# SixPotatoeV6.net
KiCad netlist of a schematic drawn in EAGLE
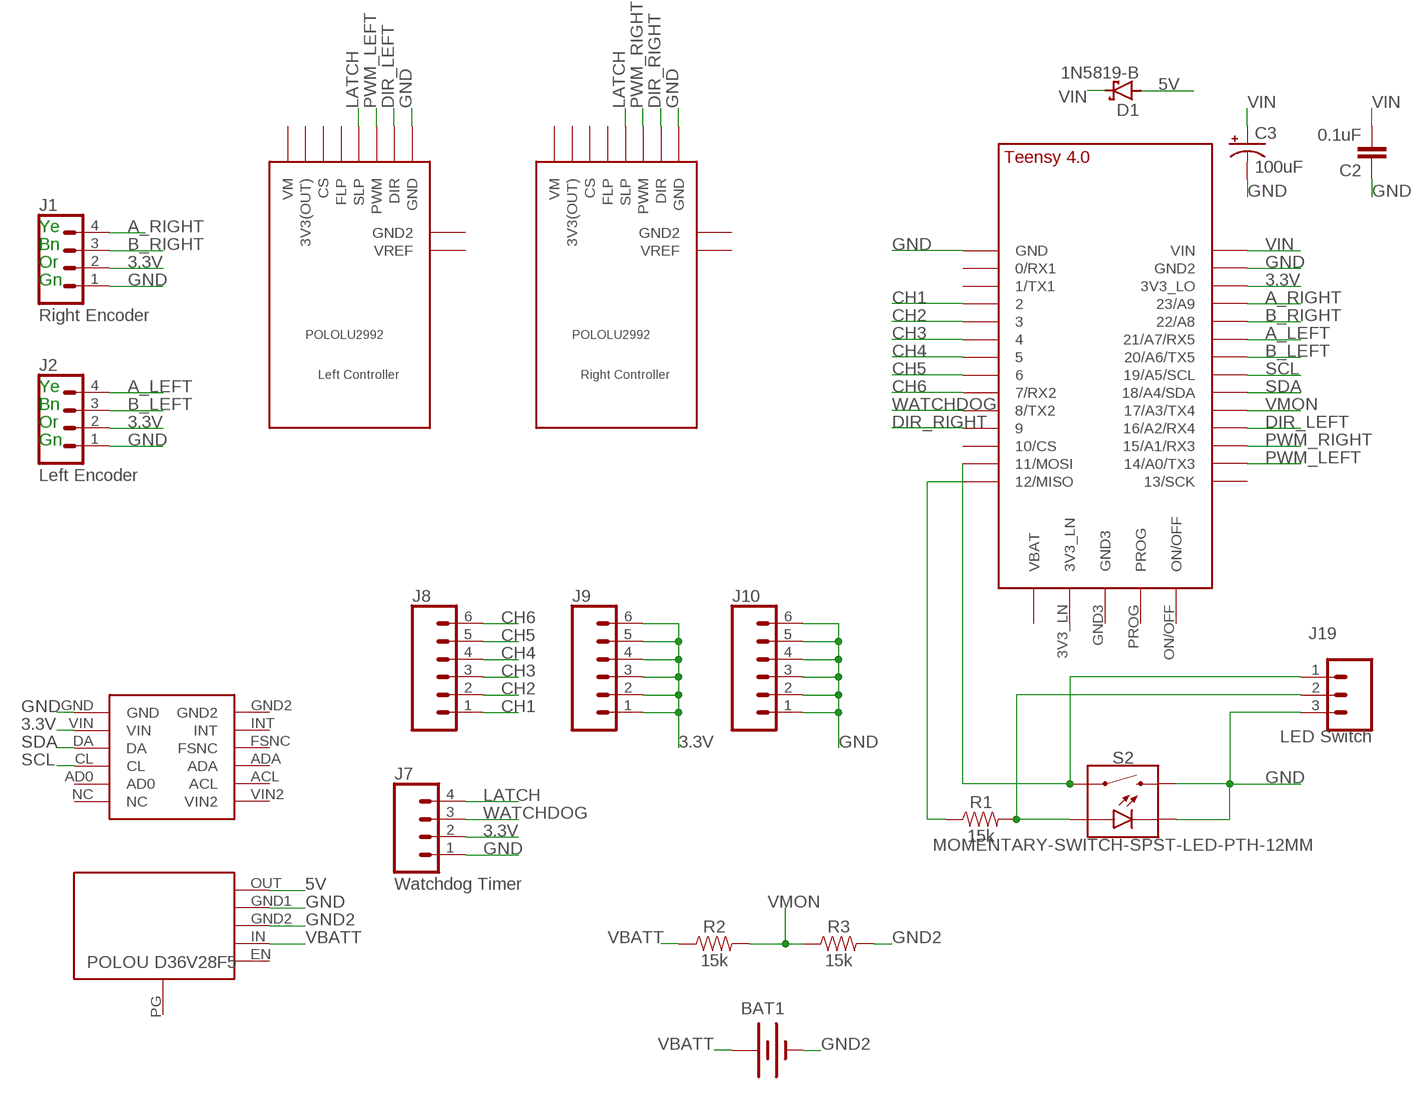
[diagram p0: schematic, sheet 1]

(export (version "E")
  (design (tool "Eeschema 10.0.6"))
  (components
    (comp (ref "BAT1")
      (value "XT60_MALE")
      (footprint "eagle-import:XT60")
      (libsource (lib "eagle-import") (part "XT60_MALE"))
    )
    (comp (ref "C2")
      (value "0.1uF")
      (footprint "eagle-import:CAP-PTH-SMALL-KIT")
      (libsource (lib "eagle-import") (part "0.1UF-KIT-EZ-50V-20%"))
    )
    (comp (ref "C3")
      (value "100uF")
      (footprint "eagle-import:CPOL-RADIAL-2.5MM-6.5MM")
      (libsource (lib "eagle-import") (part "100UF-POLAR-RADIAL-2.5MM-25V-20%"))
    )
    (comp (ref "D1")
      (value "1N5819-B")
      (footprint "eagle-import:DO41-7.6")
      (libsource (lib "eagle-import") (part "1N5819-B"))
    )
    (comp (ref "J1")
      (value "CONN_04")
      (footprint "eagle-import:1X04")
      (fields (field (name "ID") "Right Encoder"))
      (libsource (lib "eagle-import") (part "CONN_04"))
    )
    (comp (ref "J2")
      (value "CONN_04")
      (footprint "eagle-import:1X04")
      (fields (field (name "ID") "Left Encoder"))
      (libsource (lib "eagle-import") (part "CONN_04"))
    )
    (comp (ref "J7")
      (value "CONN_04")
      (footprint "eagle-import:1X04")
      (fields (field (name "ID") "Watchdog Timer"))
      (libsource (lib "eagle-import") (part "CONN_04"))
    )
    (comp (ref "J8")
      (value "CONN_06NO_SILK_FEMALE_PTH")
      (footprint "eagle-import:1X06_NO_SILK")
      (libsource (lib "eagle-import") (part "CONN_06NO_SILK_FEMALE_PTH"))
    )
    (comp (ref "J9")
      (value "CONN_06NO_SILK_FEMALE_PTH")
      (footprint "eagle-import:1X06_NO_SILK")
      (libsource (lib "eagle-import") (part "CONN_06NO_SILK_FEMALE_PTH"))
    )
    (comp (ref "J10")
      (value "CONN_06NO_SILK_FEMALE_PTH")
      (footprint "eagle-import:1X06_NO_SILK")
      (libsource (lib "eagle-import") (part "CONN_06NO_SILK_FEMALE_PTH"))
    )
    (comp (ref "J19")
      (value "CONN_03")
      (footprint "eagle-import:1X03")
      (fields (field (name "ID") "LED Switch"))
      (libsource (lib "eagle-import") (part "CONN_03"))
    )
    (comp (ref "R1")
      (value "15k")
      (footprint "eagle-import:AXIAL-0.3")
      (libsource (lib "eagle-import") (part "15KOHM-HORIZ-1/4W-5%"))
    )
    (comp (ref "R2")
      (value "15k")
      (footprint "eagle-import:AXIAL-0.3")
      (libsource (lib "eagle-import") (part "15KOHM-HORIZ-1/4W-5%"))
    )
    (comp (ref "R3")
      (value "15k")
      (footprint "eagle-import:AXIAL-0.3")
      (libsource (lib "eagle-import") (part "15KOHM-HORIZ-1/4W-5%"))
    )
    (comp (ref "S2")
      (value "MOMENTARY-SWITCH-SPST-LED-PTH-12MM")
      (footprint "eagle-import:TACTILE_SWITCH_LED_PTH_12MM")
      (libsource (lib "eagle-import") (part "MOMENTARY-SWITCH-SPST-LED-PTH-12MM"))
    )
    (comp (ref "U$1")
      (value "TEENSY_4.0")
      (footprint "eagle-import:TEENSY_4.0")
      (libsource (lib "eagle-import") (part "TEENSY_4.0"))
    )
    (comp (ref "U$2")
      (value "Left Controller")
      (footprint "eagle-import:POLOLU2992_2")
      (libsource (lib "eagle-import") (part "POLOLU2992_2"))
    )
    (comp (ref "U$3")
      (value "Right Controller")
      (footprint "eagle-import:POLOLU2992_2")
      (libsource (lib "eagle-import") (part "POLOLU2992_2"))
    )
    (comp (ref "U$4")
      (value "POLOU3782")
      (footprint "eagle-import:POLOU3782")
      (libsource (lib "eagle-import") (part "POLOU3782"))
    )
    (comp (ref "U$5")
      (value "SEN15335")
      (footprint "eagle-import:SEN15335")
      (libsource (lib "eagle-import") (part "SEN15335"))
    )
  )
  (nets
    (net (code "1") (name "/3.3V") (class "Default")
      (node (ref "J1") (pin "2") (pinfunction "2_2") (pintype "passive"))
      (node (ref "J2") (pin "2") (pinfunction "2_2") (pintype "passive"))
      (node (ref "J7") (pin "2") (pinfunction "2_2") (pintype "passive"))
      (node (ref "J9") (pin "1") (pinfunction "1_1") (pintype "passive"))
      (node (ref "J9") (pin "2") (pinfunction "2_2") (pintype "passive"))
      (node (ref "J9") (pin "3") (pinfunction "3_3") (pintype "passive"))
      (node (ref "J9") (pin "4") (pinfunction "4_4") (pintype "passive"))
      (node (ref "J9") (pin "5") (pinfunction "5_5") (pintype "passive"))
      (node (ref "J9") (pin "6") (pinfunction "6_6") (pintype "passive"))
      (node (ref "U$1") (pin "3V3_LO") (pinfunction "3V3_LO_3V3_LO") (pintype "bidirectional"))
      (node (ref "U$5") (pin "VIN") (pinfunction "VIN_VIN") (pintype "bidirectional"))
    )
    (net (code "2") (name "/5V") (class "Default")
      (node (ref "D1") (pin "A") (pinfunction "A_A") (pintype "passive"))
      (node (ref "U$4") (pin "OUT") (pinfunction "OUT_OUT") (pintype "bidirectional"))
    )
    (net (code "3") (name "/A_LEFT") (class "Default")
      (node (ref "J2") (pin "4") (pinfunction "4_4") (pintype "passive"))
      (node (ref "U$1") (pin "21/A7") (pinfunction "21/A7/RX5_21/A7") (pintype "bidirectional"))
    )
    (net (code "4") (name "/A_RIGHT") (class "Default")
      (node (ref "J1") (pin "4") (pinfunction "4_4") (pintype "passive"))
      (node (ref "U$1") (pin "23/A9") (pinfunction "23/A9_23/A9") (pintype "bidirectional"))
    )
    (net (code "5") (name "/B_LEFT") (class "Default")
      (node (ref "J2") (pin "3") (pinfunction "3_3") (pintype "passive"))
      (node (ref "U$1") (pin "20/A6") (pinfunction "20/A6/TX5_20/A6") (pintype "bidirectional"))
    )
    (net (code "6") (name "/B_RIGHT") (class "Default")
      (node (ref "J1") (pin "3") (pinfunction "3_3") (pintype "passive"))
      (node (ref "U$1") (pin "22/A8") (pinfunction "22/A8_22/A8") (pintype "bidirectional"))
    )
    (net (code "7") (name "/CH1") (class "Default")
      (node (ref "J8") (pin "1") (pinfunction "1_1") (pintype "passive"))
      (node (ref "U$1") (pin "2") (pinfunction "2_2") (pintype "bidirectional"))
    )
    (net (code "8") (name "/CH2") (class "Default")
      (node (ref "J8") (pin "2") (pinfunction "2_2") (pintype "passive"))
      (node (ref "U$1") (pin "3/CANTX") (pinfunction "3_3/CANTX") (pintype "bidirectional"))
    )
    (net (code "9") (name "/CH3") (class "Default")
      (node (ref "J8") (pin "3") (pinfunction "3_3") (pintype "passive"))
      (node (ref "U$1") (pin "4/CANRX") (pinfunction "4_4/CANRX") (pintype "bidirectional"))
    )
    (net (code "10") (name "/CH4") (class "Default")
      (node (ref "J8") (pin "4") (pinfunction "4_4") (pintype "passive"))
      (node (ref "U$1") (pin "5") (pinfunction "5_5") (pintype "bidirectional"))
    )
    (net (code "11") (name "/CH5") (class "Default")
      (node (ref "J8") (pin "5") (pinfunction "5_5") (pintype "passive"))
      (node (ref "U$1") (pin "6") (pinfunction "6_6") (pintype "bidirectional"))
    )
    (net (code "12") (name "/CH6") (class "Default")
      (node (ref "J8") (pin "6") (pinfunction "6_6") (pintype "passive"))
      (node (ref "U$1") (pin "7") (pinfunction "7/RX2_7") (pintype "bidirectional"))
    )
    (net (code "13") (name "/DIR_LEFT") (class "Default")
      (node (ref "U$1") (pin "16/A2") (pinfunction "16/A2/RX4_16/A2") (pintype "bidirectional"))
      (node (ref "U$2") (pin "DIR") (pinfunction "DIR_DIR") (pintype "bidirectional"))
    )
    (net (code "14") (name "/DIR_RIGHT") (class "Default")
      (node (ref "U$1") (pin "9/CS") (pinfunction "9_9/CS") (pintype "bidirectional"))
      (node (ref "U$3") (pin "DIR") (pinfunction "DIR_DIR") (pintype "bidirectional"))
    )
    (net (code "15") (name "/GND") (class "Default")
      (node (ref "C2") (pin "1") (pinfunction "1_1") (pintype "passive"))
      (node (ref "C3") (pin "2") (pinfunction "-_2") (pintype "passive"))
      (node (ref "J1") (pin "1") (pinfunction "1_1") (pintype "passive"))
      (node (ref "J10") (pin "1") (pinfunction "1_1") (pintype "passive"))
      (node (ref "J10") (pin "2") (pinfunction "2_2") (pintype "passive"))
      (node (ref "J10") (pin "3") (pinfunction "3_3") (pintype "passive"))
      (node (ref "J10") (pin "4") (pinfunction "4_4") (pintype "passive"))
      (node (ref "J10") (pin "5") (pinfunction "5_5") (pintype "passive"))
      (node (ref "J10") (pin "6") (pinfunction "6_6") (pintype "passive"))
      (node (ref "J19") (pin "3") (pinfunction "3_3") (pintype "passive"))
      (node (ref "J2") (pin "1") (pinfunction "1_1") (pintype "passive"))
      (node (ref "J7") (pin "1") (pinfunction "1_1") (pintype "passive"))
      (node (ref "S2") (pin "2") (pinfunction "2_2") (pintype "passive"))
      (node (ref "S2") (pin "C") (pinfunction "C_C") (pintype "passive"))
      (node (ref "U$1") (pin "GND") (pinfunction "GND_GND") (pintype "bidirectional"))
      (node (ref "U$1") (pin "GND2") (pinfunction "GND2_GND2") (pintype "bidirectional"))
      (node (ref "U$2") (pin "GND") (pinfunction "GND_GND") (pintype "bidirectional"))
      (node (ref "U$3") (pin "GND") (pinfunction "GND_GND") (pintype "bidirectional"))
      (node (ref "U$4") (pin "GND1") (pinfunction "GND1_GND1") (pintype "bidirectional"))
      (node (ref "U$5") (pin "GND") (pinfunction "GND_GND") (pintype "bidirectional"))
    )
    (net (code "16") (name "/GND2") (class "Default")
      (node (ref "BAT1") (pin "-") (pinfunction "-_-") (pintype "power_in"))
      (node (ref "R3") (pin "P$2") (pinfunction "2_P$2") (pintype "passive"))
      (node (ref "U$4") (pin "GND2") (pinfunction "GND2_GND2") (pintype "bidirectional"))
    )
    (net (code "17") (name "/LATCH") (class "Default")
      (node (ref "J7") (pin "4") (pinfunction "4_4") (pintype "passive"))
      (node (ref "U$2") (pin "SLP") (pinfunction "SLP_SLP") (pintype "bidirectional"))
      (node (ref "U$3") (pin "SLP") (pinfunction "SLP_SLP") (pintype "bidirectional"))
    )
    (net (code "18") (name "/PWM_LEFT") (class "Default")
      (node (ref "U$1") (pin "14/A0") (pinfunction "14/A0/TX3_14/A0") (pintype "bidirectional"))
      (node (ref "U$2") (pin "PWM") (pinfunction "PWM_PWM") (pintype "bidirectional"))
    )
    (net (code "19") (name "/PWM_RIGHT") (class "Default")
      (node (ref "U$1") (pin "15/A1") (pinfunction "15/A1/RX3_15/A1") (pintype "bidirectional"))
      (node (ref "U$3") (pin "PWM") (pinfunction "PWM_PWM") (pintype "bidirectional"))
    )
    (net (code "20") (name "/SCL") (class "Default")
      (node (ref "U$1") (pin "19/A5/SCL") (pinfunction "19/A5/SCL_19/A5/SCL") (pintype "bidirectional"))
      (node (ref "U$5") (pin "CL") (pinfunction "CL_CL") (pintype "bidirectional"))
    )
    (net (code "21") (name "/SDA") (class "Default")
      (node (ref "U$1") (pin "18/A4/SDA") (pinfunction "18/A4/SDA_18/A4/SDA") (pintype "bidirectional"))
      (node (ref "U$5") (pin "DA") (pinfunction "DA_DA") (pintype "bidirectional"))
    )
    (net (code "22") (name "/VBATT") (class "Default")
      (node (ref "BAT1") (pin "+") (pinfunction "+_+") (pintype "power_in"))
      (node (ref "R2") (pin "P$1") (pinfunction "1_P$1") (pintype "passive"))
      (node (ref "U$4") (pin "IN") (pinfunction "IN_IN") (pintype "bidirectional"))
    )
    (net (code "23") (name "/VIN") (class "Default")
      (node (ref "C2") (pin "2") (pinfunction "2_2") (pintype "passive"))
      (node (ref "C3") (pin "1") (pinfunction "+_1") (pintype "passive"))
      (node (ref "D1") (pin "C") (pinfunction "C_C") (pintype "passive"))
      (node (ref "U$1") (pin "VIN") (pinfunction "VIN_VIN") (pintype "bidirectional"))
    )
    (net (code "24") (name "/VMON") (class "Default")
      (node (ref "R2") (pin "P$2") (pinfunction "2_P$2") (pintype "passive"))
      (node (ref "R3") (pin "P$1") (pinfunction "1_P$1") (pintype "passive"))
      (node (ref "U$1") (pin "17/A3") (pinfunction "17/A3/TX4_17/A3") (pintype "bidirectional"))
    )
    (net (code "25") (name "/WATCHDOG") (class "Default")
      (node (ref "J7") (pin "3") (pinfunction "3_3") (pintype "passive"))
      (node (ref "U$1") (pin "8") (pinfunction "8/TX2_8") (pintype "bidirectional"))
    )
    (net (code "26") (name "Net-(R1-1)") (class "Default")
      (node (ref "R1") (pin "P$1") (pinfunction "1_P$1") (pintype "passive"))
      (node (ref "U$1") (pin "12/MISO") (pinfunction "12/MISO_12/MISO") (pintype "bidirectional"))
    )
    (net (code "27") (name "Net-(R1-2)") (class "Default")
      (node (ref "J19") (pin "2") (pinfunction "2_2") (pintype "passive"))
      (node (ref "R1") (pin "P$2") (pinfunction "2_P$2") (pintype "passive"))
      (node (ref "S2") (pin "A") (pinfunction "A_A") (pintype "passive"))
    )
    (net (code "28") (name "Net-(S2-1)") (class "Default")
      (node (ref "J19") (pin "1") (pinfunction "1_1") (pintype "passive"))
      (node (ref "S2") (pin "4") (pinfunction "1_4") (pintype "passive"))
      (node (ref "U$1") (pin "11/MOSI") (pinfunction "11/MOSI_11/MOSI") (pintype "bidirectional"))
    )
    (net (code "29") (name "unconnected-(U$1-0{slash}RX1-Pad0{slash}RX)") (class "Default")
      (node (ref "U$1") (pin "0/RX") (pinfunction "0/RX1_0/RX") (pintype "bidirectional"))
    )
    (net (code "30") (name "unconnected-(U$1-1{slash}TX1-Pad1{slash}TX)") (class "Default")
      (node (ref "U$1") (pin "1/TX") (pinfunction "1/TX1_1/TX") (pintype "bidirectional"))
    )
    (net (code "31") (name "unconnected-(U$1-Pad3V3_LN)") (class "Default")
      (node (ref "U$1") (pin "3V3_LN") (pinfunction "3V3_LN_3V3_LN") (pintype "bidirectional"))
    )
    (net (code "32") (name "unconnected-(U$1-Pad10{slash}CS)") (class "Default")
      (node (ref "U$1") (pin "10/CS") (pinfunction "10/CS_10/CS") (pintype "bidirectional"))
    )
    (net (code "33") (name "unconnected-(U$1-Pad13{slash}SCK)") (class "Default")
      (node (ref "U$1") (pin "13/SCK") (pinfunction "13/SCK_13/SCK") (pintype "bidirectional"))
    )
    (net (code "34") (name "unconnected-(U$1-PadGND3)") (class "Default")
      (node (ref "U$1") (pin "GND3") (pinfunction "GND3_GND3") (pintype "bidirectional"))
    )
    (net (code "35") (name "unconnected-(U$1-PadON{slash}OFF)") (class "Default")
      (node (ref "U$1") (pin "ON/OFF") (pinfunction "ON/OFF_ON/OFF") (pintype "bidirectional"))
    )
    (net (code "36") (name "unconnected-(U$1-PadPROG)") (class "Default")
      (node (ref "U$1") (pin "PROG") (pinfunction "PROG_PROG") (pintype "bidirectional"))
    )
    (net (code "37") (name "unconnected-(U$1-VBAT-PadVBAT\\)") (class "Default")
      (node (ref "U$1") (pin "VBAT\\") (pinfunction "VBAT_VBAT\\") (pintype "bidirectional"))
    )
    (net (code "38") (name "unconnected-(U$2-Pad3V3(OUT))") (class "Default")
      (node (ref "U$2") (pin "3V3(OUT)") (pinfunction "3V3(OUT)_3V3(OUT)") (pintype "bidirectional"))
    )
    (net (code "39") (name "unconnected-(U$2-PadCS)") (class "Default")
      (node (ref "U$2") (pin "CS") (pinfunction "CS_CS") (pintype "bidirectional"))
    )
    (net (code "40") (name "unconnected-(U$2-PadFLP)") (class "Default")
      (node (ref "U$2") (pin "FLP") (pinfunction "FLP_FLP") (pintype "bidirectional"))
    )
    (net (code "41") (name "unconnected-(U$2-PadGND2)") (class "Default")
      (node (ref "U$2") (pin "GND2") (pinfunction "GND2_GND2") (pintype "bidirectional"))
    )
    (net (code "42") (name "unconnected-(U$2-PadVM)") (class "Default")
      (node (ref "U$2") (pin "VM") (pinfunction "VM_VM") (pintype "bidirectional"))
    )
    (net (code "43") (name "unconnected-(U$2-PadVREF)") (class "Default")
      (node (ref "U$2") (pin "VREF") (pinfunction "VREF_VREF") (pintype "bidirectional"))
    )
    (net (code "44") (name "unconnected-(U$3-Pad3V3(OUT))") (class "Default")
      (node (ref "U$3") (pin "3V3(OUT)") (pinfunction "3V3(OUT)_3V3(OUT)") (pintype "bidirectional"))
    )
    (net (code "45") (name "unconnected-(U$3-PadCS)") (class "Default")
      (node (ref "U$3") (pin "CS") (pinfunction "CS_CS") (pintype "bidirectional"))
    )
    (net (code "46") (name "unconnected-(U$3-PadFLP)") (class "Default")
      (node (ref "U$3") (pin "FLP") (pinfunction "FLP_FLP") (pintype "bidirectional"))
    )
    (net (code "47") (name "unconnected-(U$3-PadGND2)") (class "Default")
      (node (ref "U$3") (pin "GND2") (pinfunction "GND2_GND2") (pintype "bidirectional"))
    )
    (net (code "48") (name "unconnected-(U$3-PadVM)") (class "Default")
      (node (ref "U$3") (pin "VM") (pinfunction "VM_VM") (pintype "bidirectional"))
    )
    (net (code "49") (name "unconnected-(U$3-PadVREF)") (class "Default")
      (node (ref "U$3") (pin "VREF") (pinfunction "VREF_VREF") (pintype "bidirectional"))
    )
    (net (code "50") (name "unconnected-(U$4-PadEN)") (class "Default")
      (node (ref "U$4") (pin "EN") (pinfunction "EN_EN") (pintype "bidirectional"))
    )
    (net (code "51") (name "unconnected-(U$4-PadPG)") (class "Default")
      (node (ref "U$4") (pin "PG") (pinfunction "PG_PG") (pintype "bidirectional"))
    )
    (net (code "52") (name "unconnected-(U$5-PadACL)") (class "Default")
      (node (ref "U$5") (pin "ACL") (pinfunction "ACL_ACL") (pintype "bidirectional"))
    )
    (net (code "53") (name "unconnected-(U$5-PadAD0)") (class "Default")
      (node (ref "U$5") (pin "AD0") (pinfunction "AD0_AD0") (pintype "bidirectional"))
    )
    (net (code "54") (name "unconnected-(U$5-PadADA)") (class "Default")
      (node (ref "U$5") (pin "ADA") (pinfunction "ADA_ADA") (pintype "bidirectional"))
    )
    (net (code "55") (name "unconnected-(U$5-PadFSNC)") (class "Default")
      (node (ref "U$5") (pin "FSNC") (pinfunction "FSNC_FSNC") (pintype "bidirectional"))
    )
    (net (code "56") (name "unconnected-(U$5-PadGND2)") (class "Default")
      (node (ref "U$5") (pin "GND2") (pinfunction "GND2_GND2") (pintype "bidirectional"))
    )
    (net (code "57") (name "unconnected-(U$5-PadINT)") (class "Default")
      (node (ref "U$5") (pin "INT") (pinfunction "INT_INT") (pintype "bidirectional"))
    )
    (net (code "58") (name "unconnected-(U$5-PadNC)") (class "Default")
      (node (ref "U$5") (pin "NC") (pinfunction "NC_NC") (pintype "bidirectional"))
    )
    (net (code "59") (name "unconnected-(U$5-PadVIN2)") (class "Default")
      (node (ref "U$5") (pin "VIN2") (pinfunction "VIN2_VIN2") (pintype "bidirectional"))
    )
  )
)
